# STM32H70VBT6_Schematics.net
KiCad netlist of a schematic drawn in Altium Designer
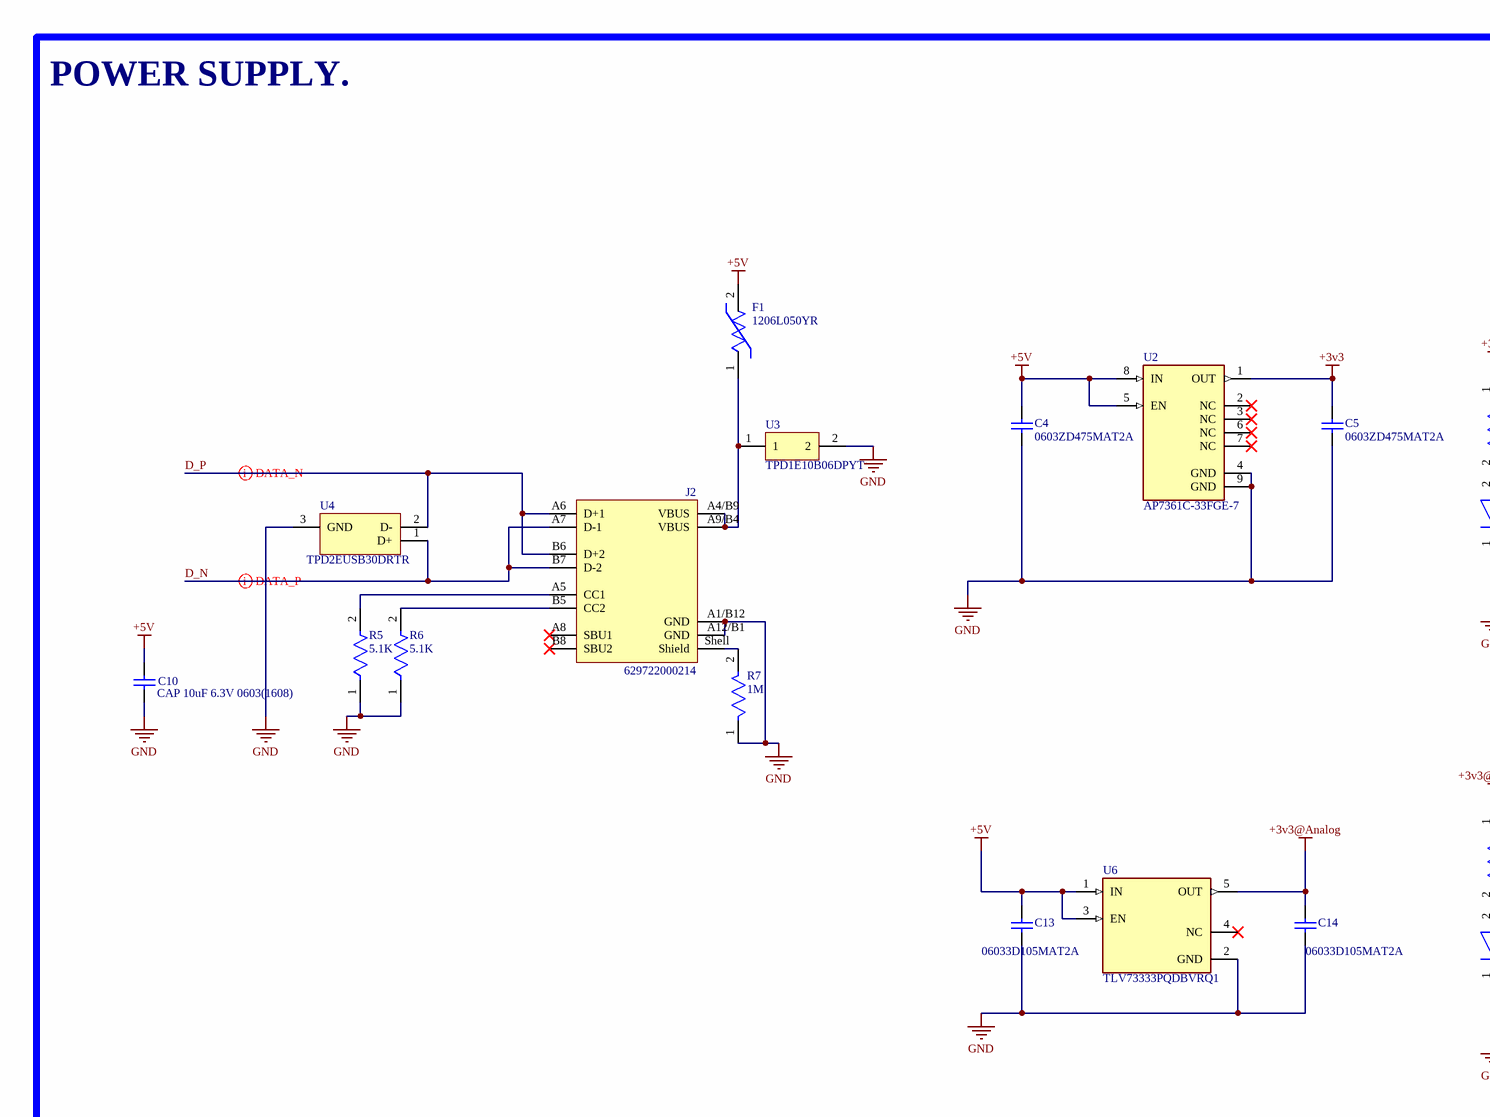
[diagram p0: STM32H70VBT6 Schematics.SchDoc, left]
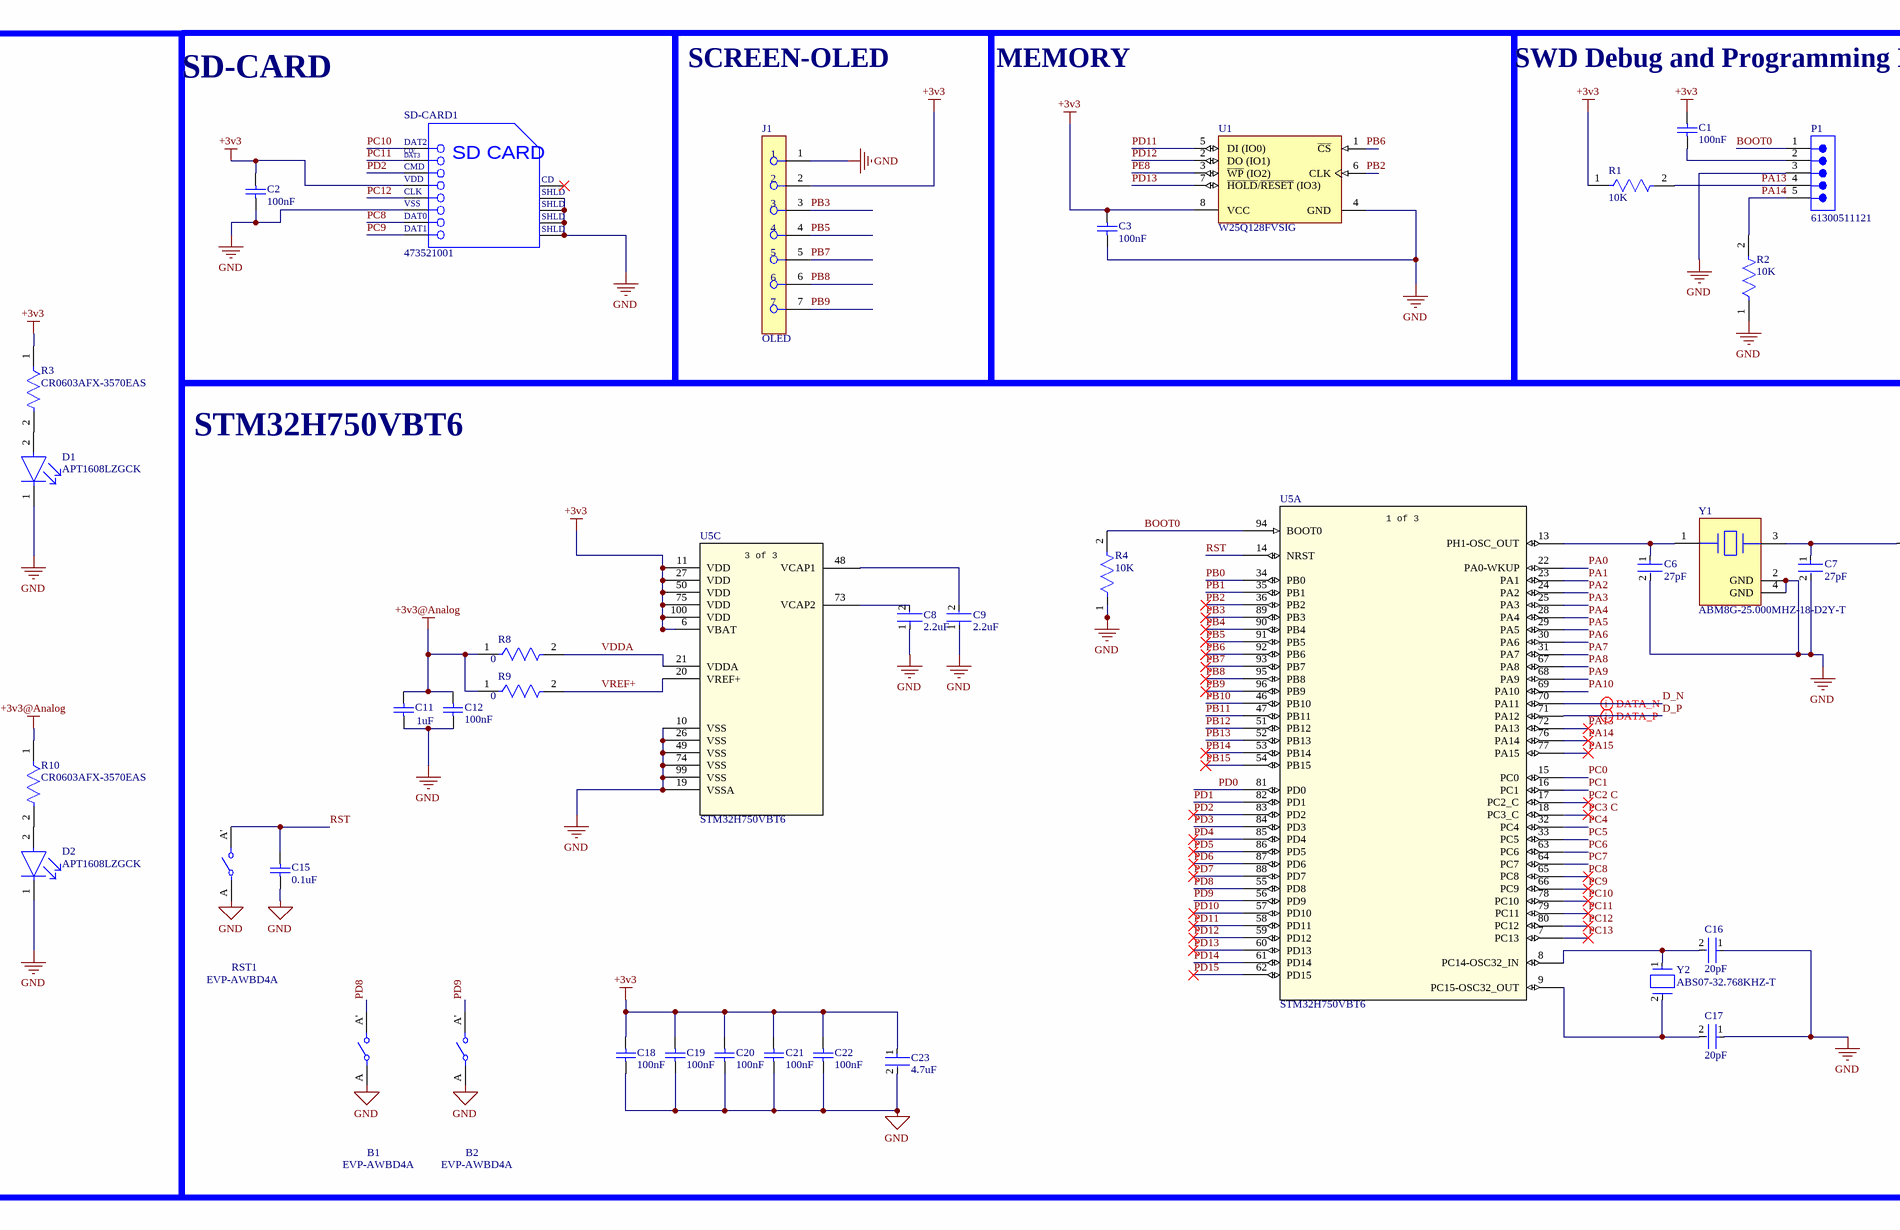
[diagram p1: STM32H70VBT6 Schematics.SchDoc, middle]
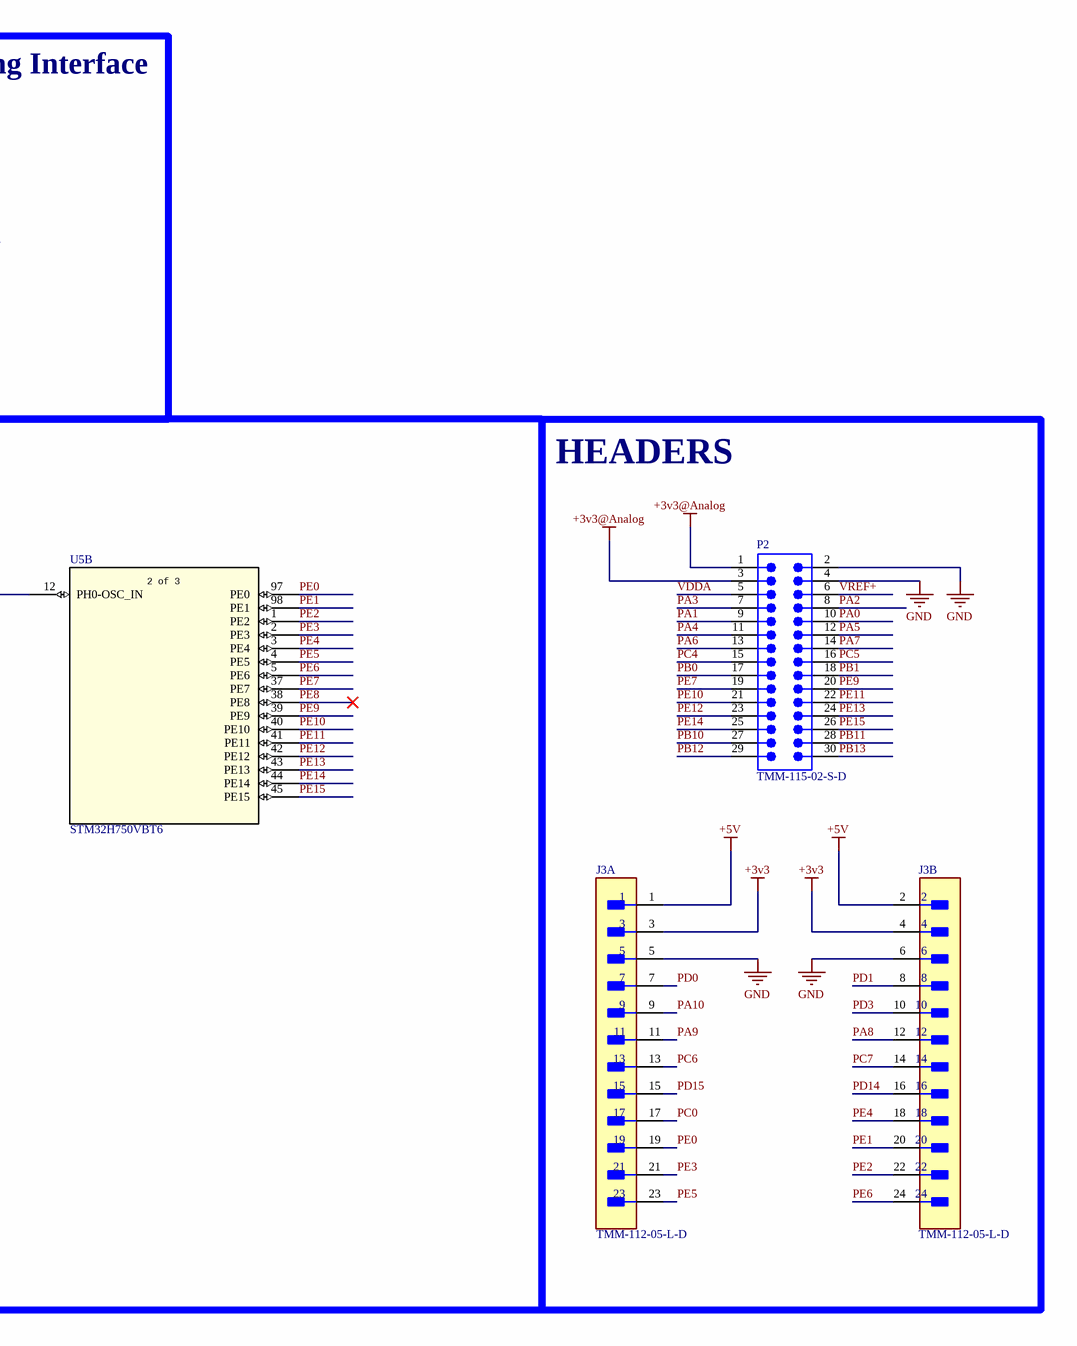
[diagram p2: STM32H70VBT6 Schematics.SchDoc, right]

(export (version "E")
  (design (tool "Eeschema 10.0.6"))
  (components
    (comp (ref "B1")
      (value "EVP-AWBD4A")
      (footprint "FP-EVP-AWBD4A-MFG")
      (description "3.0MM X 2.0MM / 1.6N / 0.13MM ST")
      (libsource (lib "Altium Content Vault") (part "33768b6a6d39f0e4b166fb985f98e2e"))
    )
    (comp (ref "B2")
      (value "EVP-AWBD4A")
      (footprint "FP-EVP-AWBD4A-MFG")
      (description "3.0MM X 2.0MM / 1.6N / 0.13MM ST")
      (libsource (lib "Altium Content Vault") (part "33768b6a6d39f0e4b166fb985f98e2e"))
    )
    (comp (ref "C1")
      (value "100nF")
      (footprint "CAPC0603(1608)100_L")
      (description "CAP 100nF 10V ±5% 0603 (1608 Metric) Thickness 1mm SMD")
      (fields (field (name "TOLERANCE") "Â±5%"))
      (libsource (lib "Altium Content Vault") (part "CAP"))
    )
    (comp (ref "C2")
      (value "100nF")
      (footprint "CAPC0603(1608)100_L")
      (description "CAP 100nF 10V ±5% 0603 (1608 Metric) Thickness 1mm SMD")
      (fields (field (name "TOLERANCE") "Â±5%"))
      (libsource (lib "Altium Content Vault") (part "CAP"))
    )
    (comp (ref "C3")
      (value "100nF")
      (footprint "CAPC0603(1608)100_L")
      (description "CAP 100nF 10V ±5% 0603 (1608 Metric) Thickness 1mm SMD")
      (fields (field (name "TOLERANCE") "Â±5%"))
      (libsource (lib "Altium Content Vault") (part "CAP"))
    )
    (comp (ref "C4")
      (value "0603ZD475MAT2A")
      (footprint "CAPC1608X90X35NL15T15")
      (fields (field (name "MANUFACTURER") "AVX Interconnect / Elco"))
      (libsource (lib "Altium Content Vault") (part "CAP"))
    )
    (comp (ref "C5")
      (value "0603ZD475MAT2A")
      (footprint "CAPC1608X90X35NL15T15")
      (fields (field (name "MANUFACTURER") "AVX Interconnect / Elco"))
      (libsource (lib "Altium Content Vault") (part "CAP"))
    )
    (comp (ref "C6")
      (value "27pF")
      (footprint "FP-AC0402-0_5-MFG")
      (description "Cap Ceramic 27pF 50V C0G 5% SMD 0402 125°C Paper T/R")
      (fields (field (name "MANUFACTURER PART NUMBER") "AC0402JRNPO9BN270") (field (name "TOLERANCE") "0.05"))
      (libsource (lib "Altium Content Vault") (part "11868f565c42a9108669ba33697ecf6"))
    )
    (comp (ref "C7")
      (value "27pF")
      (footprint "FP-AC0402-0_5-MFG")
      (description "Cap Ceramic 27pF 50V C0G 5% SMD 0402 125°C Paper T/R")
      (fields (field (name "MANUFACTURER PART NUMBER") "AC0402JRNPO9BN270") (field (name "TOLERANCE") "0.05"))
      (libsource (lib "Altium Content Vault") (part "11868f565c42a9108669ba33697ecf6"))
    )
    (comp (ref "C8")
      (value "2.2uF")
      (footprint "FP-CC0603-DA-MFG")
      (description "CC0603 2.2 uF X5R 10.00% 16 V")
      (fields
        (field (name "MANUFACTURER") "YAGEO")
        (field (name "MANUFACTURER PART NUMBER") "CC0603KPX5R7BB225")
      )
      (libsource (lib "Altium Content Vault") (part "11868f565c42a9108669ba33697ecf6"))
    )
    (comp (ref "C9")
      (value "2.2uF")
      (footprint "FP-CC0603-DA-MFG")
      (description "CC0603 2.2 uF X5R 10.00% 16 V")
      (fields
        (field (name "MANUFACTURER") "YAGEO")
        (field (name "MANUFACTURER PART NUMBER") "CC0603KPX5R7BB225")
      )
      (libsource (lib "Altium Content Vault") (part "11868f565c42a9108669ba33697ecf6"))
    )
    (comp (ref "C10")
      (value "CAP 10uF 6.3V 0603(1608)")
      (footprint "CAPC0603(1608)100_M")
      (description "CAP 10uF 6.3V ±10% 0603 (1608 Metric) Thickness 1mm SMD")
      (fields (field (name "TOLERANCE") "Â±10%"))
      (libsource (lib "Altium Content Vault") (part "CAP"))
    )
    (comp (ref "C11")
      (value "1uF")
      (footprint "CAPC1608X90X35LL15T15")
      (fields
        (field (name "PART NUMBER") "06033D105MAT2A")
        (field (name "MANUFACTURER") "AVX Interconnect / Elco")
      )
      (libsource (lib "Altium Content Vault") (part "CAP"))
    )
    (comp (ref "C12")
      (value "100nF")
      (footprint "CAPC0603(1608)100_L")
      (description "CAP 100nF 10V ±5% 0603 (1608 Metric) Thickness 1mm SMD")
      (fields (field (name "TOLERANCE") "Â±5%"))
      (libsource (lib "Altium Content Vault") (part "CAP"))
    )
    (comp (ref "C13")
      (value "06033D105MAT2A")
      (footprint "CAPC1608X90X35LL15T15")
      (fields (field (name "MANUFACTURER") "AVX Interconnect / Elco"))
      (libsource (lib "Altium Content Vault") (part "CAP"))
    )
    (comp (ref "C14")
      (value "06033D105MAT2A")
      (footprint "CAPC1608X90X35LL15T15")
      (fields (field (name "MANUFACTURER") "AVX Interconnect / Elco"))
      (libsource (lib "Altium Content Vault") (part "CAP"))
    )
    (comp (ref "C15")
      (value "0.1uF")
      (footprint "CAPC0603(1608)100_L")
      (description "CAP 100nF 10V ±5% 0603 (1608 Metric) Thickness 1mm SMD")
      (fields (field (name "TOLERANCE") "Â±5%"))
      (libsource (lib "Altium Content Vault") (part "CAP"))
    )
    (comp (ref "C16")
      (value "20pF")
      (footprint "FP-C0603C-CF-MFG")
      (description "CAP CER 20PF 100V NP0 0603")
      (fields
        (field (name "TOLERANCE") "0.25 pF")
        (field (name "MANUFACTURER PART NUMBER") "C0603C200C1GACTU")
      )
      (libsource (lib "Altium Content Vault") (part "b4654b650e69147ec39a6b967a45e02"))
    )
    (comp (ref "C17")
      (value "20pF")
      (footprint "FP-C0603C-CF-MFG")
      (description "CAP CER 20PF 100V NP0 0603")
      (fields
        (field (name "TOLERANCE") "0.25 pF")
        (field (name "MANUFACTURER PART NUMBER") "C0603C200C1GACTU")
      )
      (libsource (lib "Altium Content Vault") (part "b4654b650e69147ec39a6b967a45e02"))
    )
    (comp (ref "C18")
      (value "100nF")
      (footprint "CAPC0603(1608)100_L")
      (description "CAP 100nF 10V ±5% 0603 (1608 Metric) Thickness 1mm SMD")
      (fields (field (name "TOLERANCE") "Â±5%"))
      (libsource (lib "Altium Content Vault") (part "CAP"))
    )
    (comp (ref "C19")
      (value "100nF")
      (footprint "CAPC0603(1608)100_L")
      (description "CAP 100nF 10V ±5% 0603 (1608 Metric) Thickness 1mm SMD")
      (fields (field (name "TOLERANCE") "Â±5%"))
      (libsource (lib "Altium Content Vault") (part "CAP"))
    )
    (comp (ref "C20")
      (value "100nF")
      (footprint "CAPC0603(1608)100_L")
      (description "CAP 100nF 10V ±5% 0603 (1608 Metric) Thickness 1mm SMD")
      (fields (field (name "TOLERANCE") "Â±5%"))
      (libsource (lib "Altium Content Vault") (part "CAP"))
    )
    (comp (ref "C21")
      (value "100nF")
      (footprint "CAPC0603(1608)100_L")
      (description "CAP 100nF 10V ±5% 0603 (1608 Metric) Thickness 1mm SMD")
      (fields (field (name "TOLERANCE") "Â±5%"))
      (libsource (lib "Altium Content Vault") (part "CAP"))
    )
    (comp (ref "C22")
      (value "100nF")
      (footprint "CAPC0603(1608)100_L")
      (description "CAP 100nF 10V ±5% 0603 (1608 Metric) Thickness 1mm SMD")
      (fields (field (name "TOLERANCE") "Â±5%"))
      (libsource (lib "Altium Content Vault") (part "CAP"))
    )
    (comp (ref "C23")
      (value "4.7uF")
      (footprint "FP-CC0603-DA-MFG")
      (description "CC0603 4.7 uF X5R 10.00% 6.3 V")
      (fields
        (field (name "MANUFACTURER") "YAGEO")
        (field (name "OCTOPART") "https://octopart.com/cc0603kpx5r5bb475-yageo-75168911")
      )
      (libsource (lib "Altium Content Vault") (part "11868f565c42a9108669ba33697ecf6"))
    )
    (comp (ref "D1")
      (value "APT1608LZGCK")
      (footprint "FP-APT1608LZGCK-MFG")
      (description "LED GREEN CLEAR 2SMD")
      (libsource (lib "Altium Content Vault") (part "8706943c75ba83719d021d2fdc84c58"))
    )
    (comp (ref "D2")
      (value "APT1608LZGCK")
      (footprint "FP-APT1608LZGCK-MFG")
      (description "LED GREEN CLEAR 2SMD")
      (libsource (lib "Altium Content Vault") (part "8706943c75ba83719d021d2fdc84c58"))
    )
    (comp (ref "F1")
      (value "1206L050YR")
      (footprint "FP-1206L050YR-MFG")
      (description "PTC RESET FUSE 6V 500MA 1206")
      (libsource (lib "Altium Content Vault") (part "fdf083d5f6389a9a1c4e51137f46658"))
    )
    (comp (ref "J1")
      (value "OLED")
      (footprint "FP-LPPB071NFFN-RC-MFG")
      (description "LPPB071NFFN-RC .050 Female Header 1 Row 1x07 pins Straight")
      (libsource (lib "Altium Content Vault") (part "e5664c6fdf629e95b354a88b8d4375b"))
    )
    (comp (ref "J2")
      (value "629722000214")
      (footprint "629722000214")
      (description "Usb Conn, R/a, Type C 2.0, Rcpt, 16POS Rohs Compliant: Yes")
      (libsource (lib "Altium Content Vault") (part "USB 2.0_Type C_Receptacle_1 Port_629722000214"))
    )
    (comp (ref "J3")
      (value "TMM-112-05-L-D")
      (footprint "FP-TMM-112-05-L-D-MFG")
      (description "2MM TERMINAL STRIP")
      (libsource (lib "") (part "00fa07415dca09057f8828961643b10_1"))
    )
    (comp (ref "P1")
      (value "61300511121")
      (footprint "61300511121")
      (description "THT Vertical Pin Header WR-PHD, Pitch 2.54 mm, Single Row, 5 pins")
      (libsource (lib "Altium Content Vault") (part "Header_Male_1R_05P"))
    )
    (comp (ref "P2")
      (value "TMM-115-02-S-D")
      (footprint "SMTC-TMM-115-02-X-D")
      (description "Low Profile Through-Hole Header, Vertical, -55 to 125 degC, 2 mm Pitch, 30-Pin, Male, RoHS")
      (fields (field (name "MANUFACTURER") "Samtec"))
      (libsource (lib "Altium Content Vault") (part "SMTC-TMM-115-02-X-D"))
    )
    (comp (ref "R1")
      (value "10K")
      (footprint "FP-AC0603-IPC_A")
      (description "RES 10kΩ 5.00% 0.2W 0603")
      (libsource (lib "Altium Content Vault") (part "1029c3af85768c4190bb7ad29bc67b5"))
    )
    (comp (ref "R2")
      (value "10K")
      (footprint "FP-AC0603-IPC_A")
      (description "RES 10kΩ 5.00% 0.2W 0603")
      (libsource (lib "Altium Content Vault") (part "1029c3af85768c4190bb7ad29bc67b5"))
    )
    (comp (ref "R3")
      (value "CR0603AFX-3570EAS")
      (footprint "FP-CR0603-IPC_C")
      (description "Sulfur-Resistant, AEC-Q200 Compliant Chip Resistors 0603 357Ω 0.1W 1% 100ppm/°C")
      (libsource (lib "Altium Content Vault") (part "1029c3af85768c4190bb7ad29bc67b5"))
    )
    (comp (ref "R4")
      (value "10K")
      (footprint "FP-AC0603-IPC_A")
      (description "RES 10kΩ 5.00% 0.2W 0603")
      (libsource (lib "Altium Content Vault") (part "1029c3af85768c4190bb7ad29bc67b5"))
    )
    (comp (ref "R5")
      (value "5.1K")
      (footprint "FP-RN73R1E-IPC_C")
      (description "5.1kΩ ±1% 0.063W, 1/16W Chip Resistor 0402 (1005 Metric) Moisture Resistant Thin Film")
      (libsource (lib "Altium Content Vault") (part "1029c3af85768c4190bb7ad29bc67b5"))
    )
    (comp (ref "R6")
      (value "5.1K")
      (footprint "FP-RN73R1E-IPC_C")
      (description "5.1kΩ ±1% 0.063W, 1/16W Chip Resistor 0402 (1005 Metric) Moisture Resistant Thin Film")
      (libsource (lib "Altium Content Vault") (part "1029c3af85768c4190bb7ad29bc67b5"))
    )
    (comp (ref "R7")
      (value "1M")
      (footprint "FP-CRGP0603-IPC_C")
      (description "RES 1M OHM 1% 1/4W 0603")
      (fields (field (name "TOLERANCE") "1%"))
      (libsource (lib "Altium Content Vault") (part "1029c3af85768c4190bb7ad29bc67b5"))
    )
    (comp (ref "R8")
      (value "0")
      (footprint "FP-AC0603-IPC_A")
      (description "RES 0Ω 0.00% 0.1W 0603")
      (fields (field (name "TOLERANCE") "5%"))
      (libsource (lib "Altium Content Vault") (part "1029c3af85768c4190bb7ad29bc67b5"))
    )
    (comp (ref "R9")
      (value "0")
      (footprint "FP-AC0603-IPC_A")
      (description "RES 0Ω 0.00% 0.1W 0603")
      (fields (field (name "TOLERANCE") "5%"))
      (libsource (lib "Altium Content Vault") (part "1029c3af85768c4190bb7ad29bc67b5"))
    )
    (comp (ref "R10")
      (value "CR0603AFX-3570EAS")
      (footprint "FP-CR0603-IPC_C")
      (description "Sulfur-Resistant, AEC-Q200 Compliant Chip Resistors 0603 357Ω 0.1W 1% 100ppm/°C")
      (libsource (lib "Altium Content Vault") (part "1029c3af85768c4190bb7ad29bc67b5"))
    )
    (comp (ref "RST1")
      (value "EVP-AWBD4A")
      (footprint "FP-EVP-AWBD4A-MFG")
      (description "3.0MM X 2.0MM / 1.6N / 0.13MM ST")
      (libsource (lib "Altium Content Vault") (part "33768b6a6d39f0e4b166fb985f98e2e"))
    )
    (comp (ref "SD-CARD1")
      (value "473521001")
      (footprint "MOLX-473521001_V")
      (description "MicroSD(TM), Pitch 1.1 mm, 8 Position, Height 1.88 mm, -20 to 85 degC, RoHS, Tape and Reel")
      (fields (field (name "MANUFACTURER") "Molex"))
      (libsource (lib "Altium Content Vault") (part "CN-SD-8-1SW-4S"))
    )
    (comp (ref "U1")
      (value "W25Q128FVSIG")
      (footprint "WINB-SOIC-8_M")
      (fields (field (name "MANUFACTURER") "Winbond"))
      (libsource (lib "Altium Content Vault") (part "WINB-W25Q128FVSIG-SOIC-8"))
    )
    (comp (ref "U2")
      (value "AP7361C-33FGE-7")
      (footprint "FP-U-DFN3030-8_Type_E-MFG")
      (description "IC REG LINEAR 3.3V 1A UDFN3030-8")
      (fields
        (field (name "MANUFACTURER") "Diodes Inc.")
        (field (name "OCTOPART") "https://octopart.com/ap7361c-33fge-7-diodes+inc.-65869522")
      )
      (libsource (lib "Altium Content Vault") (part "2971fe8480f7e8815ea3c3920f93e3e"))
    )
    (comp (ref "U3")
      (value "TPD1E10B06DPYT")
      (footprint "DPY0002A_L")
      (fields (field (name "MANUFACTURER") "Texas Instruments"))
      (libsource (lib "Altium Content Vault") (part "TI-TPD1E10B06-X2SON_DPY-2"))
    )
    (comp (ref "U4")
      (value "TPD2EUSB30DRTR")
      (footprint "DRT0003A")
      (fields (field (name "MANUFACTURER") "Texas Instruments"))
      (libsource (lib "Altium Content Vault") (part "TI-TPD2EUSB30-SOT_DRT-3"))
    )
    (comp (ref "U5")
      (value "STM32H750VBT6")
      (footprint "QFP50P1600X1600X160-100N")
      (fields (field (name "COPYRIGHT") "Copyright (C) 2025 Ultra Librarian. All rights reserved."))
      (libsource (lib "STM32H750VBT6") (part "STM32H750VBT6"))
    )
    (comp (ref "U6")
      (value "TLV73333PQDBVRQ1")
      (footprint "FP-DBV0005A-IPC_A")
      (description "IC REG LINEAR 3.3V 300MA SOT23-5")
      (libsource (lib "Altium Content Vault") (part "9fe5a7569a672cc344d83ad3dd2d204"))
    )
    (comp (ref "Y1")
      (value "ABM8G-25.000MHZ-18-D2Y-T")
      (footprint "FP-ABM8G-MFG")
      (description "Crystal 25MHz ±20ppm (Tol) ±30ppm (Stability) 18pF FUND 60Ω 4-Pin SMD T/R")
      (fields (field (name "TOLERANCE") "20ppm"))
      (libsource (lib "Altium Content Vault") (part "48e526d86b7f2615d98721063c72f49"))
    )
    (comp (ref "Y2")
      (value "ABS07-32.768KHZ-T")
      (footprint "FP-ABS07-MFG")
      (description "Crystal 32.768kHz ±20ppm (Tol) 12.5pF FUND 70kΩ 2-Pin CSMD T/R")
      (fields (field (name "TOLERANCE") "20ppm"))
      (libsource (lib "Altium Content Vault") (part "c23a69dc6c9e2f18f2079038eb95dd1"))
    )
  )
  (nets
    (net (code "1") (name "+3v3") (class "Default")
      (node (ref "C1") (pin "2") (pinfunction "2_2") (pintype "passive"))
      (node (ref "C18") (pin "2") (pinfunction "2_2") (pintype "passive"))
      (node (ref "C19") (pin "2") (pinfunction "2_2") (pintype "passive"))
      (node (ref "C2") (pin "2") (pinfunction "2_2") (pintype "passive"))
      (node (ref "C20") (pin "2") (pinfunction "2_2") (pintype "passive"))
      (node (ref "C21") (pin "2") (pinfunction "2_2") (pintype "passive"))
      (node (ref "C22") (pin "2") (pinfunction "2_2") (pintype "passive"))
      (node (ref "C23") (pin "1") (pinfunction "1_1") (pintype "passive"))
      (node (ref "C3") (pin "2") (pinfunction "2_2") (pintype "passive"))
      (node (ref "C5") (pin "2") (pinfunction "2_2") (pintype "passive"))
      (node (ref "J1") (pin "2") (pinfunction "2_2") (pintype "passive"))
      (node (ref "J3") (pin "3") (pinfunction "3_3") (pintype "passive"))
      (node (ref "J3") (pin "4") (pinfunction "4_4") (pintype "passive"))
      (node (ref "R1") (pin "1") (pinfunction "1_1") (pintype "passive"))
      (node (ref "R3") (pin "1") (pinfunction "1_1") (pintype "passive"))
      (node (ref "SD-CARD1") (pin "4") (pinfunction "VDD_4") (pintype "passive"))
      (node (ref "U1") (pin "8") (pinfunction "VCC_8") (pintype "power_in"))
      (node (ref "U2") (pin "1") (pinfunction "OUT_1") (pintype "output"))
      (node (ref "U5") (pin "100") (pinfunction "VDD_100") (pintype "power_in"))
      (node (ref "U5") (pin "11") (pinfunction "VDD_11") (pintype "power_in"))
      (node (ref "U5") (pin "27") (pinfunction "VDD_27") (pintype "power_in"))
      (node (ref "U5") (pin "50") (pinfunction "VDD_50") (pintype "power_in"))
      (node (ref "U5") (pin "6") (pinfunction "VBAT_6") (pintype "power_in"))
      (node (ref "U5") (pin "75") (pinfunction "VDD_75") (pintype "power_in"))
    )
    (net (code "2") (name "+3v3@Analog") (class "Default")
      (node (ref "C11") (pin "2") (pinfunction "2_2") (pintype "passive"))
      (node (ref "C12") (pin "2") (pinfunction "2_2") (pintype "passive"))
      (node (ref "C14") (pin "2") (pinfunction "2_2") (pintype "passive"))
      (node (ref "P2") (pin "1") (pinfunction "1_1") (pintype "passive"))
      (node (ref "P2") (pin "3") (pinfunction "3_3") (pintype "passive"))
      (node (ref "R10") (pin "1") (pinfunction "1_1") (pintype "passive"))
      (node (ref "R8") (pin "1") (pinfunction "1_1") (pintype "passive"))
      (node (ref "R9") (pin "1") (pinfunction "1_1") (pintype "passive"))
      (node (ref "U6") (pin "5") (pinfunction "OUT_5") (pintype "output"))
    )
    (net (code "3") (name "+5V") (class "Default")
      (node (ref "C10") (pin "2") (pinfunction "2_2") (pintype "passive"))
      (node (ref "C13") (pin "2") (pinfunction "2_2") (pintype "passive"))
      (node (ref "C4") (pin "2") (pinfunction "2_2") (pintype "passive"))
      (node (ref "F1") (pin "2") (pinfunction "2_2") (pintype "passive"))
      (node (ref "J3") (pin "1") (pinfunction "1_1") (pintype "passive"))
      (node (ref "J3") (pin "2") (pinfunction "2_2") (pintype "passive"))
      (node (ref "U2") (pin "5") (pinfunction "EN_5") (pintype "input"))
      (node (ref "U2") (pin "8") (pinfunction "IN_8") (pintype "input"))
      (node (ref "U6") (pin "1") (pinfunction "IN_1") (pintype "input"))
      (node (ref "U6") (pin "3") (pinfunction "EN_3") (pintype "input"))
    )
    (net (code "4") (name "/BOOT0") (class "Default")
      (node (ref "P1") (pin "1") (pinfunction "1_1") (pintype "passive"))
      (node (ref "R4") (pin "2") (pinfunction "2_2") (pintype "passive"))
      (node (ref "U5") (pin "94") (pinfunction "BOOT0_94") (pintype "input"))
    )
    (net (code "5") (name "/D_N") (class "Default")
      (node (ref "J2") (pin "A7") (pinfunction "D-1_A7") (pintype "passive"))
      (node (ref "J2") (pin "B7") (pinfunction "D-2_B7") (pintype "passive"))
      (node (ref "U4") (pin "1") (pinfunction "D+_1") (pintype "passive"))
      (node (ref "U5") (pin "70") (pinfunction "PA11_70") (pintype "bidirectional"))
    )
    (net (code "6") (name "/D_P") (class "Default")
      (node (ref "J2") (pin "A6") (pinfunction "D+1_A6") (pintype "passive"))
      (node (ref "J2") (pin "B6") (pinfunction "D+2_B6") (pintype "passive"))
      (node (ref "U4") (pin "2") (pinfunction "D-_2") (pintype "passive"))
      (node (ref "U5") (pin "71") (pinfunction "PA12_71") (pintype "bidirectional"))
    )
    (net (code "7") (name "/PA0") (class "Default")
      (node (ref "P2") (pin "10") (pinfunction "10_10") (pintype "passive"))
      (node (ref "U5") (pin "22") (pinfunction "PA0-WKUP_22") (pintype "bidirectional"))
    )
    (net (code "8") (name "/PA1") (class "Default")
      (node (ref "P2") (pin "9") (pinfunction "9_9") (pintype "passive"))
      (node (ref "U5") (pin "23") (pinfunction "PA1_23") (pintype "bidirectional"))
    )
    (net (code "9") (name "/PA2") (class "Default")
      (node (ref "P2") (pin "8") (pinfunction "8_8") (pintype "passive"))
      (node (ref "U5") (pin "24") (pinfunction "PA2_24") (pintype "bidirectional"))
    )
    (net (code "10") (name "/PA3") (class "Default")
      (node (ref "P2") (pin "7") (pinfunction "7_7") (pintype "passive"))
      (node (ref "U5") (pin "25") (pinfunction "PA3_25") (pintype "bidirectional"))
    )
    (net (code "11") (name "/PA4") (class "Default")
      (node (ref "P2") (pin "11") (pinfunction "11_11") (pintype "passive"))
      (node (ref "U5") (pin "28") (pinfunction "PA4_28") (pintype "bidirectional"))
    )
    (net (code "12") (name "/PA5") (class "Default")
      (node (ref "P2") (pin "12") (pinfunction "12_12") (pintype "passive"))
      (node (ref "U5") (pin "29") (pinfunction "PA5_29") (pintype "bidirectional"))
    )
    (net (code "13") (name "/PA6") (class "Default")
      (node (ref "P2") (pin "13") (pinfunction "13_13") (pintype "passive"))
      (node (ref "U5") (pin "30") (pinfunction "PA6_30") (pintype "bidirectional"))
    )
    (net (code "14") (name "/PA7") (class "Default")
      (node (ref "P2") (pin "14") (pinfunction "14_14") (pintype "passive"))
      (node (ref "U5") (pin "31") (pinfunction "PA7_31") (pintype "bidirectional"))
    )
    (net (code "15") (name "/PA8") (class "Default")
      (node (ref "J3") (pin "12") (pinfunction "12_12") (pintype "passive"))
      (node (ref "U5") (pin "67") (pinfunction "PA8_67") (pintype "bidirectional"))
    )
    (net (code "16") (name "/PA9") (class "Default")
      (node (ref "J3") (pin "11") (pinfunction "11_11") (pintype "passive"))
      (node (ref "U5") (pin "68") (pinfunction "PA9_68") (pintype "bidirectional"))
    )
    (net (code "17") (name "/PA10") (class "Default")
      (node (ref "J3") (pin "9") (pinfunction "9_9") (pintype "passive"))
      (node (ref "U5") (pin "69") (pinfunction "PA10_69") (pintype "bidirectional"))
    )
    (net (code "18") (name "/PA13") (class "Default")
      (node (ref "P1") (pin "4") (pinfunction "4_4") (pintype "passive"))
      (node (ref "R1") (pin "2") (pinfunction "2_2") (pintype "passive"))
      (node (ref "U5") (pin "72") (pinfunction "PA13_72") (pintype "bidirectional"))
    )
    (net (code "19") (name "/PA14") (class "Default")
      (node (ref "P1") (pin "5") (pinfunction "5_5") (pintype "passive"))
      (node (ref "R2") (pin "2") (pinfunction "2_2") (pintype "passive"))
      (node (ref "U5") (pin "76") (pinfunction "PA14_76") (pintype "bidirectional"))
    )
    (net (code "20") (name "/PA15") (class "Default")
      (node (ref "U5") (pin "77") (pinfunction "PA15_77") (pintype "bidirectional+no_connect"))
    )
    (net (code "21") (name "/PB0") (class "Default")
      (node (ref "P2") (pin "17") (pinfunction "17_17") (pintype "passive"))
      (node (ref "U5") (pin "34") (pinfunction "PB0_34") (pintype "bidirectional"))
    )
    (net (code "22") (name "/PB1") (class "Default")
      (node (ref "P2") (pin "18") (pinfunction "18_18") (pintype "passive"))
      (node (ref "U5") (pin "35") (pinfunction "PB1_35") (pintype "bidirectional"))
    )
    (net (code "23") (name "/PB2") (class "Default")
      (node (ref "U1") (pin "6") (pinfunction "CLK_6") (pintype "input"))
      (node (ref "U5") (pin "36") (pinfunction "PB2_36") (pintype "bidirectional"))
    )
    (net (code "24") (name "/PB3") (class "Default")
      (node (ref "J1") (pin "3") (pinfunction "3_3") (pintype "passive"))
      (node (ref "U5") (pin "89") (pinfunction "PB3_89") (pintype "bidirectional"))
    )
    (net (code "25") (name "/PB4") (class "Default")
      (node (ref "U5") (pin "90") (pinfunction "PB4_90") (pintype "bidirectional+no_connect"))
    )
    (net (code "26") (name "/PB5") (class "Default")
      (node (ref "J1") (pin "4") (pinfunction "4_4") (pintype "passive"))
      (node (ref "U5") (pin "91") (pinfunction "PB5_91") (pintype "bidirectional"))
    )
    (net (code "27") (name "/PB6") (class "Default")
      (node (ref "U1") (pin "1") (pinfunction "~{CS}_1") (pintype "input"))
      (node (ref "U5") (pin "92") (pinfunction "PB6_92") (pintype "bidirectional"))
    )
    (net (code "28") (name "/PB7") (class "Default")
      (node (ref "J1") (pin "5") (pinfunction "5_5") (pintype "passive"))
      (node (ref "U5") (pin "93") (pinfunction "PB7_93") (pintype "bidirectional"))
    )
    (net (code "29") (name "/PB8") (class "Default")
      (node (ref "J1") (pin "6") (pinfunction "6_6") (pintype "passive"))
      (node (ref "U5") (pin "95") (pinfunction "PB8_95") (pintype "bidirectional"))
    )
    (net (code "30") (name "/PB9") (class "Default")
      (node (ref "J1") (pin "7") (pinfunction "7_7") (pintype "passive"))
      (node (ref "U5") (pin "96") (pinfunction "PB9_96") (pintype "bidirectional"))
    )
    (net (code "31") (name "/PB10") (class "Default")
      (node (ref "P2") (pin "27") (pinfunction "27_27") (pintype "passive"))
      (node (ref "U5") (pin "46") (pinfunction "PB10_46") (pintype "bidirectional"))
    )
    (net (code "32") (name "/PB11") (class "Default")
      (node (ref "P2") (pin "28") (pinfunction "28_28") (pintype "passive"))
      (node (ref "U5") (pin "47") (pinfunction "PB11_47") (pintype "bidirectional"))
    )
    (net (code "33") (name "/PB12") (class "Default")
      (node (ref "P2") (pin "29") (pinfunction "29_29") (pintype "passive"))
      (node (ref "U5") (pin "51") (pinfunction "PB12_51") (pintype "bidirectional"))
    )
    (net (code "34") (name "/PB13") (class "Default")
      (node (ref "P2") (pin "30") (pinfunction "30_30") (pintype "passive"))
      (node (ref "U5") (pin "52") (pinfunction "PB13_52") (pintype "bidirectional"))
    )
    (net (code "35") (name "/PB14") (class "Default")
      (node (ref "U5") (pin "53") (pinfunction "PB14_53") (pintype "bidirectional+no_connect"))
    )
    (net (code "36") (name "/PB15") (class "Default")
      (node (ref "U5") (pin "54") (pinfunction "PB15_54") (pintype "bidirectional+no_connect"))
    )
    (net (code "37") (name "/PC0") (class "Default")
      (node (ref "J3") (pin "17") (pinfunction "17_17") (pintype "passive"))
      (node (ref "U5") (pin "15") (pinfunction "PC0_15") (pintype "bidirectional"))
    )
    (net (code "38") (name "/PC1") (class "Default")
      (node (ref "U5") (pin "16") (pinfunction "PC1_16") (pintype "bidirectional"))
    )
    (net (code "39") (name "/PC2 C") (class "Default")
      (node (ref "U5") (pin "17") (pinfunction "PC2_C_17") (pintype "bidirectional+no_connect"))
    )
    (net (code "40") (name "/PC3 C") (class "Default")
      (node (ref "U5") (pin "18") (pinfunction "PC3_C_18") (pintype "bidirectional+no_connect"))
    )
    (net (code "41") (name "/PC4") (class "Default")
      (node (ref "P2") (pin "15") (pinfunction "15_15") (pintype "passive"))
      (node (ref "U5") (pin "32") (pinfunction "PC4_32") (pintype "bidirectional"))
    )
    (net (code "42") (name "/PC5") (class "Default")
      (node (ref "P2") (pin "16") (pinfunction "16_16") (pintype "passive"))
      (node (ref "U5") (pin "33") (pinfunction "PC5_33") (pintype "bidirectional"))
    )
    (net (code "43") (name "/PC6") (class "Default")
      (node (ref "J3") (pin "13") (pinfunction "13_13") (pintype "passive"))
      (node (ref "U5") (pin "63") (pinfunction "PC6_63") (pintype "bidirectional"))
    )
    (net (code "44") (name "/PC7") (class "Default")
      (node (ref "J3") (pin "14") (pinfunction "14_14") (pintype "passive"))
      (node (ref "U5") (pin "64") (pinfunction "PC7_64") (pintype "bidirectional"))
    )
    (net (code "45") (name "/PC8") (class "Default")
      (node (ref "SD-CARD1") (pin "7") (pinfunction "DAT0_7") (pintype "passive"))
      (node (ref "U5") (pin "65") (pinfunction "PC8_65") (pintype "bidirectional"))
    )
    (net (code "46") (name "/PC9") (class "Default")
      (node (ref "SD-CARD1") (pin "8") (pinfunction "DAT1_8") (pintype "passive"))
      (node (ref "U5") (pin "66") (pinfunction "PC9_66") (pintype "bidirectional"))
    )
    (net (code "47") (name "/PC10") (class "Default")
      (node (ref "SD-CARD1") (pin "1") (pinfunction "DAT2_1") (pintype "passive"))
      (node (ref "U5") (pin "78") (pinfunction "PC10_78") (pintype "bidirectional"))
    )
    (net (code "48") (name "/PC11") (class "Default")
      (node (ref "SD-CARD1") (pin "2") (pinfunction "CD/DAT3_2") (pintype "passive"))
      (node (ref "U5") (pin "79") (pinfunction "PC11_79") (pintype "bidirectional"))
    )
    (net (code "49") (name "/PC12") (class "Default")
      (node (ref "SD-CARD1") (pin "5") (pinfunction "CLK_5") (pintype "passive"))
      (node (ref "U5") (pin "80") (pinfunction "PC12_80") (pintype "bidirectional"))
    )
    (net (code "50") (name "/PC13") (class "Default")
      (node (ref "U5") (pin "7") (pinfunction "PC13_7") (pintype "bidirectional+no_connect"))
    )
    (net (code "51") (name "/PD0") (class "Default")
      (node (ref "J3") (pin "7") (pinfunction "7_7") (pintype "passive"))
      (node (ref "U5") (pin "81") (pinfunction "PD0_81") (pintype "bidirectional"))
    )
    (net (code "52") (name "/PD1") (class "Default")
      (node (ref "J3") (pin "8") (pinfunction "8_8") (pintype "passive"))
      (node (ref "U5") (pin "82") (pinfunction "PD1_82") (pintype "bidirectional"))
    )
    (net (code "53") (name "/PD2") (class "Default")
      (node (ref "SD-CARD1") (pin "3") (pinfunction "CMD_3") (pintype "passive"))
      (node (ref "U5") (pin "83") (pinfunction "PD2_83") (pintype "bidirectional"))
    )
    (net (code "54") (name "/PD3") (class "Default")
      (node (ref "J3") (pin "10") (pinfunction "10_10") (pintype "passive"))
      (node (ref "U5") (pin "84") (pinfunction "PD3_84") (pintype "bidirectional"))
    )
    (net (code "55") (name "/PD4") (class "Default")
      (node (ref "U5") (pin "85") (pinfunction "PD4_85") (pintype "bidirectional+no_connect"))
    )
    (net (code "56") (name "/PD5") (class "Default")
      (node (ref "U5") (pin "86") (pinfunction "PD5_86") (pintype "bidirectional+no_connect"))
    )
    (net (code "57") (name "/PD6") (class "Default")
      (node (ref "U5") (pin "87") (pinfunction "PD6_87") (pintype "bidirectional+no_connect"))
    )
    (net (code "58") (name "/PD7") (class "Default")
      (node (ref "U5") (pin "88") (pinfunction "PD7_88") (pintype "bidirectional+no_connect"))
    )
    (net (code "59") (name "/PD8") (class "Default")
      (node (ref "B1") (pin "A'") (pinfunction "A'_A'") (pintype "passive"))
      (node (ref "U5") (pin "55") (pinfunction "PD8_55") (pintype "bidirectional"))
    )
    (net (code "60") (name "/PD9") (class "Default")
      (node (ref "B2") (pin "A'") (pinfunction "A'_A'") (pintype "passive"))
      (node (ref "U5") (pin "56") (pinfunction "PD9_56") (pintype "bidirectional"))
    )
    (net (code "61") (name "/PD10") (class "Default")
      (node (ref "U5") (pin "57") (pinfunction "PD10_57") (pintype "bidirectional+no_connect"))
    )
    (net (code "62") (name "/PD11") (class "Default")
      (node (ref "U1") (pin "5") (pinfunction "DI_(IO0)_5") (pintype "bidirectional"))
      (node (ref "U5") (pin "58") (pinfunction "PD11_58") (pintype "bidirectional"))
    )
    (net (code "63") (name "/PD12") (class "Default")
      (node (ref "U1") (pin "2") (pinfunction "DO_(IO1)_2") (pintype "bidirectional"))
      (node (ref "U5") (pin "59") (pinfunction "PD12_59") (pintype "bidirectional"))
    )
    (net (code "64") (name "/PD13") (class "Default")
      (node (ref "U1") (pin "7") (pinfunction "~{HOLD}/~{RESET}_(IO3)_7") (pintype "bidirectional"))
      (node (ref "U5") (pin "60") (pinfunction "PD13_60") (pintype "bidirectional"))
    )
    (net (code "65") (name "/PD14") (class "Default")
      (node (ref "J3") (pin "16") (pinfunction "16_16") (pintype "passive"))
      (node (ref "U5") (pin "61") (pinfunction "PD14_61") (pintype "bidirectional"))
    )
    (net (code "66") (name "/PD15") (class "Default")
      (node (ref "J3") (pin "15") (pinfunction "15_15") (pintype "passive"))
      (node (ref "U5") (pin "62") (pinfunction "PD15_62") (pintype "bidirectional"))
    )
    (net (code "67") (name "/PE0") (class "Default")
      (node (ref "J3") (pin "19") (pinfunction "19_19") (pintype "passive"))
      (node (ref "U5") (pin "97") (pinfunction "PE0_97") (pintype "bidirectional"))
    )
    (net (code "68") (name "/PE1") (class "Default")
      (node (ref "J3") (pin "20") (pinfunction "20_20") (pintype "passive"))
      (node (ref "U5") (pin "98") (pinfunction "PE1_98") (pintype "bidirectional"))
    )
    (net (code "69") (name "/PE2") (class "Default")
      (node (ref "J3") (pin "22") (pinfunction "22_22") (pintype "passive"))
      (node (ref "U5") (pin "1") (pinfunction "PE2_1") (pintype "bidirectional"))
    )
    (net (code "70") (name "/PE3") (class "Default")
      (node (ref "J3") (pin "21") (pinfunction "21_21") (pintype "passive"))
      (node (ref "U5") (pin "2") (pinfunction "PE3_2") (pintype "bidirectional"))
    )
    (net (code "71") (name "/PE4") (class "Default")
      (node (ref "J3") (pin "18") (pinfunction "18_18") (pintype "passive"))
      (node (ref "U5") (pin "3") (pinfunction "PE4_3") (pintype "bidirectional"))
    )
    (net (code "72") (name "/PE5") (class "Default")
      (node (ref "J3") (pin "23") (pinfunction "23_23") (pintype "passive"))
      (node (ref "U5") (pin "4") (pinfunction "PE5_4") (pintype "bidirectional"))
    )
    (net (code "73") (name "/PE6") (class "Default")
      (node (ref "J3") (pin "24") (pinfunction "24_24") (pintype "passive"))
      (node (ref "U5") (pin "5") (pinfunction "PE6_5") (pintype "bidirectional"))
    )
    (net (code "74") (name "/PE7") (class "Default")
      (node (ref "P2") (pin "19") (pinfunction "19_19") (pintype "passive"))
      (node (ref "U5") (pin "37") (pinfunction "PE7_37") (pintype "bidirectional"))
    )
    (net (code "75") (name "/PE8") (class "Default")
      (node (ref "U1") (pin "3") (pinfunction "~{WP}_(IO2)_3") (pintype "bidirectional"))
      (node (ref "U5") (pin "38") (pinfunction "PE8_38") (pintype "bidirectional"))
    )
    (net (code "76") (name "/PE9") (class "Default")
      (node (ref "P2") (pin "20") (pinfunction "20_20") (pintype "passive"))
      (node (ref "U5") (pin "39") (pinfunction "PE9_39") (pintype "bidirectional"))
    )
    (net (code "77") (name "/PE10") (class "Default")
      (node (ref "P2") (pin "21") (pinfunction "21_21") (pintype "passive"))
      (node (ref "U5") (pin "40") (pinfunction "PE10_40") (pintype "bidirectional"))
    )
    (net (code "78") (name "/PE11") (class "Default")
      (node (ref "P2") (pin "22") (pinfunction "22_22") (pintype "passive"))
      (node (ref "U5") (pin "41") (pinfunction "PE11_41") (pintype "bidirectional"))
    )
    (net (code "79") (name "/PE12") (class "Default")
      (node (ref "P2") (pin "23") (pinfunction "23_23") (pintype "passive"))
      (node (ref "U5") (pin "42") (pinfunction "PE12_42") (pintype "bidirectional"))
    )
    (net (code "80") (name "/PE13") (class "Default")
      (node (ref "P2") (pin "24") (pinfunction "24_24") (pintype "passive"))
      (node (ref "U5") (pin "43") (pinfunction "PE13_43") (pintype "bidirectional"))
    )
    (net (code "81") (name "/PE14") (class "Default")
      (node (ref "P2") (pin "25") (pinfunction "25_25") (pintype "passive"))
      (node (ref "U5") (pin "44") (pinfunction "PE14_44") (pintype "bidirectional"))
    )
    (net (code "82") (name "/PE15") (class "Default")
      (node (ref "P2") (pin "26") (pinfunction "26_26") (pintype "passive"))
      (node (ref "U5") (pin "45") (pinfunction "PE15_45") (pintype "bidirectional"))
    )
    (net (code "83") (name "/RST") (class "Default")
      (node (ref "C15") (pin "2") (pinfunction "2_2") (pintype "passive"))
      (node (ref "RST1") (pin "A'") (pinfunction "A'_A'") (pintype "passive"))
      (node (ref "U5") (pin "14") (pinfunction "NRST_14") (pintype "bidirectional"))
    )
    (net (code "84") (name "/VDDA") (class "Default")
      (node (ref "P2") (pin "5") (pinfunction "5_5") (pintype "passive"))
      (node (ref "R8") (pin "2") (pinfunction "2_2") (pintype "passive"))
      (node (ref "U5") (pin "21") (pinfunction "VDDA_21") (pintype "power_in"))
    )
    (net (code "85") (name "/VREF+") (class "Default")
      (node (ref "P2") (pin "6") (pinfunction "6_6") (pintype "passive"))
      (node (ref "R9") (pin "2") (pinfunction "2_2") (pintype "passive"))
      (node (ref "U5") (pin "20") (pinfunction "VREF+_20") (pintype "power_in"))
    )
    (net (code "86") (name "GND") (class "Default")
      (node (ref "B1") (pin "A") (pinfunction "A_A") (pintype "passive"))
      (node (ref "B2") (pin "A") (pinfunction "A_A") (pintype "passive"))
      (node (ref "C10") (pin "1") (pinfunction "1_1") (pintype "passive"))
      (node (ref "C11") (pin "1") (pinfunction "1_1") (pintype "passive"))
      (node (ref "C12") (pin "1") (pinfunction "1_1") (pintype "passive"))
      (node (ref "C13") (pin "1") (pinfunction "1_1") (pintype "passive"))
      (node (ref "C14") (pin "1") (pinfunction "1_1") (pintype "passive"))
      (node (ref "C15") (pin "1") (pinfunction "1_1") (pintype "passive"))
      (node (ref "C16") (pin "1") (pinfunction "1_1") (pintype "passive"))
      (node (ref "C17") (pin "1") (pinfunction "1_1") (pintype "passive"))
      (node (ref "C18") (pin "1") (pinfunction "1_1") (pintype "passive"))
      (node (ref "C19") (pin "1") (pinfunction "1_1") (pintype "passive"))
      (node (ref "C2") (pin "1") (pinfunction "1_1") (pintype "passive"))
      (node (ref "C20") (pin "1") (pinfunction "1_1") (pintype "passive"))
      (node (ref "C21") (pin "1") (pinfunction "1_1") (pintype "passive"))
      (node (ref "C22") (pin "1") (pinfunction "1_1") (pintype "passive"))
      (node (ref "C23") (pin "2") (pinfunction "2_2") (pintype "passive"))
      (node (ref "C3") (pin "1") (pinfunction "1_1") (pintype "passive"))
      (node (ref "C4") (pin "1") (pinfunction "1_1") (pintype "passive"))
      (node (ref "C5") (pin "1") (pinfunction "1_1") (pintype "passive"))
      (node (ref "C6") (pin "2") (pinfunction "2_2") (pintype "passive"))
      (node (ref "C7") (pin "2") (pinfunction "2_2") (pintype "passive"))
      (node (ref "C8") (pin "1") (pinfunction "1_1") (pintype "passive"))
      (node (ref "C9") (pin "1") (pinfunction "1_1") (pintype "passive"))
      (node (ref "D1") (pin "1") (pinfunction "C_1") (pintype "passive"))
      (node (ref "D2") (pin "1") (pinfunction "C_1") (pintype "passive"))
      (node (ref "J1") (pin "1") (pinfunction "1_1") (pintype "passive"))
      (node (ref "J2") (pin "A1/B12") (pinfunction "GND_A1/B12") (pintype "passive"))
      (node (ref "J2") (pin "A12/B1") (pinfunction "GND_A12/B1") (pintype "passive"))
      (node (ref "J3") (pin "5") (pinfunction "5_5") (pintype "passive"))
      (node (ref "J3") (pin "6") (pinfunction "6_6") (pintype "passive"))
      (node (ref "P1") (pin "3") (pinfunction "3_3") (pintype "passive"))
      (node (ref "P2") (pin "2") (pinfunction "2_2") (pintype "passive"))
      (node (ref "P2") (pin "4") (pinfunction "4_4") (pintype "passive"))
      (node (ref "R2") (pin "1") (pinfunction "1_1") (pintype "passive"))
      (node (ref "R4") (pin "1") (pinfunction "1_1") (pintype "passive"))
      (node (ref "R5") (pin "1") (pinfunction "1_1") (pintype "passive"))
      (node (ref "R6") (pin "1") (pinfunction "1_1") (pintype "passive"))
      (node (ref "R7") (pin "1") (pinfunction "1_1") (pintype "passive"))
      (node (ref "RST1") (pin "A") (pinfunction "A_A") (pintype "passive"))
      (node (ref "SD-CARD1") (pin "10") (pinfunction "SHLD_10") (pintype "passive"))
      (node (ref "SD-CARD1") (pin "11") (pinfunction "SHLD_11") (pintype "passive"))
      (node (ref "SD-CARD1") (pin "12") (pinfunction "SHLD_12") (pintype "passive"))
      (node (ref "SD-CARD1") (pin "13") (pinfunction "SHLD_13") (pintype "passive"))
      (node (ref "SD-CARD1") (pin "6") (pinfunction "VSS_6") (pintype "passive"))
      (node (ref "U1") (pin "4") (pinfunction "GND_4") (pintype "power_in"))
      (node (ref "U2") (pin "4") (pinfunction "GND_4") (pintype "power_in"))
      (node (ref "U2") (pin "9") (pinfunction "GND_9") (pintype "power_in"))
      (node (ref "U3") (pin "2") (pinfunction "2_2") (pintype "passive"))
      (node (ref "U4") (pin "3") (pinfunction "GND_3") (pintype "power_in"))
      (node (ref "U5") (pin "10") (pinfunction "VSS_10") (pintype "power_in"))
      (node (ref "U5") (pin "19") (pinfunction "VSSA_19") (pintype "power_in"))
      (node (ref "U5") (pin "26") (pinfunction "VSS_26") (pintype "power_in"))
      (node (ref "U5") (pin "49") (pinfunction "VSS_49") (pintype "power_in"))
      (node (ref "U5") (pin "74") (pinfunction "VSS_74") (pintype "power_in"))
      (node (ref "U5") (pin "99") (pinfunction "VSS_99") (pintype "power_in"))
      (node (ref "U6") (pin "2") (pinfunction "GND_2") (pintype "power_in"))
      (node (ref "Y1") (pin "2") (pinfunction "GND_2") (pintype "power_in"))
      (node (ref "Y1") (pin "4") (pinfunction "GND_4") (pintype "power_in"))
    )
    (net (code "87") (name "Net-(C1-Pad1)") (class "Default")
      (node (ref "C1") (pin "1") (pinfunction "1_1") (pintype "passive"))
      (node (ref "P1") (pin "2") (pinfunction "2_2") (pintype "passive"))
    )
    (net (code "88") (name "Net-(D1-A)") (class "Default")
      (node (ref "D1") (pin "2") (pinfunction "A_2") (pintype "passive"))
      (node (ref "R3") (pin "2") (pinfunction "2_2") (pintype "passive"))
    )
    (net (code "89") (name "Net-(D2-A)") (class "Default")
      (node (ref "D2") (pin "2") (pinfunction "A_2") (pintype "passive"))
      (node (ref "R10") (pin "2") (pinfunction "2_2") (pintype "passive"))
    )
    (net (code "90") (name "Net-(F1-Pad1)") (class "Default")
      (node (ref "F1") (pin "1") (pinfunction "1_1") (pintype "passive"))
      (node (ref "J2") (pin "A4/B9") (pinfunction "VBUS_A4/B9") (pintype "passive"))
      (node (ref "J2") (pin "A9/B4") (pinfunction "VBUS_A9/B4") (pintype "passive"))
      (node (ref "U3") (pin "1") (pinfunction "1_1") (pintype "passive"))
    )
    (net (code "91") (name "Net-(J2-CC1)") (class "Default")
      (node (ref "J2") (pin "A5") (pinfunction "CC1_A5") (pintype "passive"))
      (node (ref "R5") (pin "2") (pinfunction "2_2") (pintype "passive"))
    )
    (net (code "92") (name "Net-(J2-CC2)") (class "Default")
      (node (ref "J2") (pin "B5") (pinfunction "CC2_B5") (pintype "passive"))
      (node (ref "R6") (pin "2") (pinfunction "2_2") (pintype "passive"))
    )
    (net (code "93") (name "Net-(J2-Shield)") (class "Default")
      (node (ref "J2") (pin "Shell") (pinfunction "Shield_Shell") (pintype "passive"))
      (node (ref "R7") (pin "2") (pinfunction "2_2") (pintype "passive"))
    )
    (net (code "94") (name "Net-(U5A-PC14-OSC32_IN)") (class "Default")
      (node (ref "C16") (pin "2") (pinfunction "2_2") (pintype "passive"))
      (node (ref "U5") (pin "8") (pinfunction "PC14-OSC32_IN_8") (pintype "bidirectional"))
      (node (ref "Y2") (pin "1") (pinfunction "1_1") (pintype "passive"))
    )
    (net (code "95") (name "Net-(U5A-PC15-OSC32_OUT)") (class "Default")
      (node (ref "C17") (pin "2") (pinfunction "2_2") (pintype "passive"))
      (node (ref "U5") (pin "9") (pinfunction "PC15-OSC32_OUT_9") (pintype "bidirectional"))
      (node (ref "Y2") (pin "2") (pinfunction "2_2") (pintype "passive"))
    )
    (net (code "96") (name "Net-(U5A-PH1-OSC_OUT)") (class "Default")
      (node (ref "C6") (pin "1") (pinfunction "1_1") (pintype "passive"))
      (node (ref "U5") (pin "13") (pinfunction "PH1-OSC_OUT_13") (pintype "bidirectional"))
      (node (ref "Y1") (pin "1") (pinfunction "1_1") (pintype "passive"))
    )
    (net (code "97") (name "Net-(U5B-PH0-OSC_IN)") (class "Default")
      (node (ref "C7") (pin "1") (pinfunction "1_1") (pintype "passive"))
      (node (ref "U5") (pin "12") (pinfunction "PH0-OSC_IN_12") (pintype "bidirectional"))
      (node (ref "Y1") (pin "3") (pinfunction "3_3") (pintype "passive"))
    )
    (net (code "98") (name "Net-(U5C-VCAP1)") (class "Default")
      (node (ref "C9") (pin "2") (pinfunction "2_2") (pintype "passive"))
      (node (ref "U5") (pin "48") (pinfunction "VCAP1_48") (pintype "power_in"))
    )
    (net (code "99") (name "Net-(U5C-VCAP2)") (class "Default")
      (node (ref "C8") (pin "2") (pinfunction "2_2") (pintype "passive"))
      (node (ref "U5") (pin "73") (pinfunction "VCAP2_73") (pintype "power_in"))
    )
    (net (code "100") (name "unconnected-(J2-SBU1-PadA8)") (class "Default")
      (node (ref "J2") (pin "A8") (pinfunction "SBU1_A8") (pintype "passive+no_connect"))
    )
    (net (code "101") (name "unconnected-(J2-SBU2-PadB8)") (class "Default")
      (node (ref "J2") (pin "B8") (pinfunction "SBU2_B8") (pintype "passive+no_connect"))
    )
    (net (code "102") (name "unconnected-(SD-CARD1-CD-Pad9)") (class "Default")
      (node (ref "SD-CARD1") (pin "9") (pinfunction "CD_9") (pintype "passive+no_connect"))
    )
    (net (code "103") (name "unconnected-(U2-NC-Pad2)") (class "Default")
      (node (ref "U2") (pin "2") (pinfunction "NC_2") (pintype "passive+no_connect"))
    )
    (net (code "104") (name "unconnected-(U2-NC-Pad3)") (class "Default")
      (node (ref "U2") (pin "3") (pinfunction "NC_3") (pintype "passive+no_connect"))
    )
    (net (code "105") (name "unconnected-(U2-NC-Pad6)") (class "Default")
      (node (ref "U2") (pin "6") (pinfunction "NC_6") (pintype "passive+no_connect"))
    )
    (net (code "106") (name "unconnected-(U2-NC-Pad7)") (class "Default")
      (node (ref "U2") (pin "7") (pinfunction "NC_7") (pintype "passive+no_connect"))
    )
    (net (code "107") (name "unconnected-(U6-NC-Pad4)") (class "Default")
      (node (ref "U6") (pin "4") (pinfunction "NC_4") (pintype "passive+no_connect"))
    )
  )
)
